# L298_motor_controller.net
KiCad netlist of a schematic drawn in EAGLE
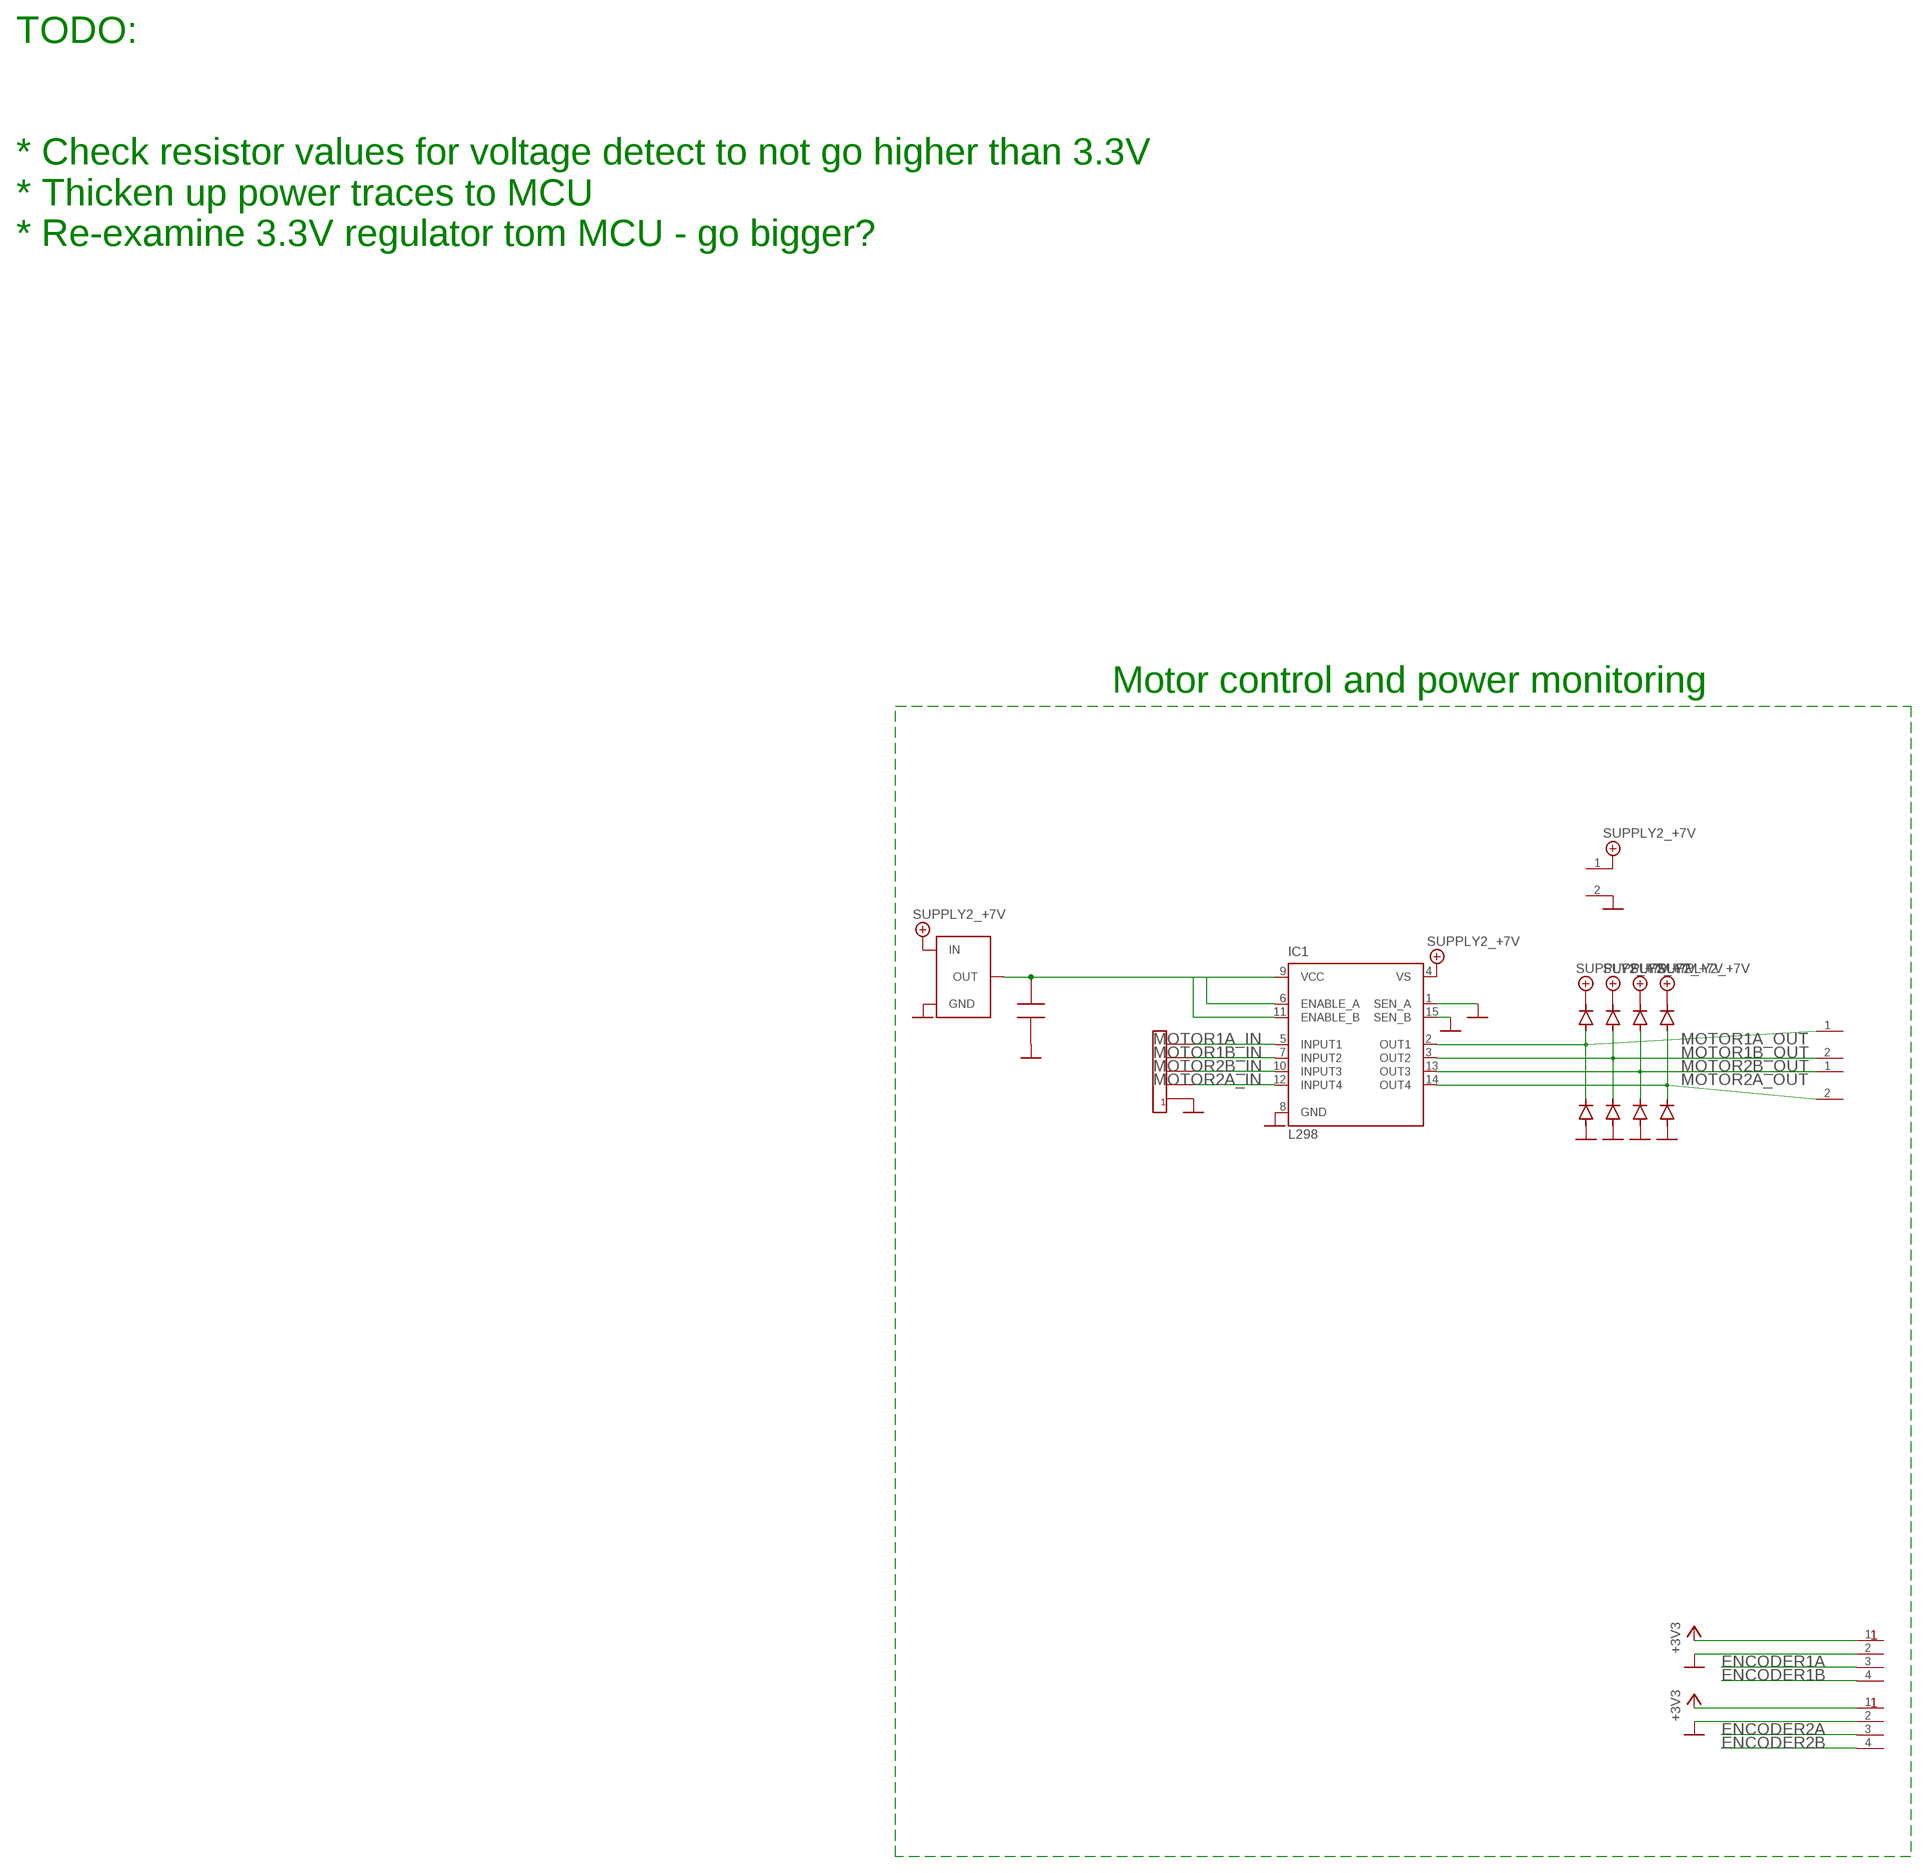
[diagram p0: schematic, sheet 1]

(export (version "E")
  (design (tool "Eeschema 10.0.6"))
  (components
    (comp (ref "IC1")
      (value "L298")
      (footprint "eagle-import:MULTIWATT-15")
      (fields (field (name "MPN") "L298N"))
      (libsource (lib "eagle-import") (part "L298"))
    )
    (comp (ref "U$1")
      (value "SCREW_TERMINAL_2_CONDUCTOR_M20109-ND")
      (footprint "eagle-import:WM20109-ND")
      (libsource (lib "eagle-import") (part "SCREW_TERMINAL_2_CONDUCTOR_M20109-ND"))
    )
    (comp (ref "U$2")
      (value "SCREW_TERMINAL_2_CONDUCTOR_M20109-ND")
      (footprint "eagle-import:WM20109-ND")
      (libsource (lib "eagle-import") (part "SCREW_TERMINAL_2_CONDUCTOR_M20109-ND"))
    )
    (comp (ref "U$3")
      (value "CONNECTOR_5_PIN")
      (footprint "eagle-import:JST_5_PIN_PH_SERIES")
      (libsource (lib "eagle-import") (part "CONNECTOR_5_PIN"))
    )
    (comp (ref "U$4")
      (value "SCREW_TERMINAL_2_CONDUCTOR_M20109-ND")
      (footprint "eagle-import:WM20109-ND")
      (libsource (lib "eagle-import") (part "SCREW_TERMINAL_2_CONDUCTOR_M20109-ND"))
    )
    (comp (ref "U$13")
      (value "DIODESOD-123FL")
      (footprint "eagle-import:SOD-123FL")
      (libsource (lib "eagle-import") (part "DIODESOD-123FL"))
    )
    (comp (ref "U$14")
      (value "DIODESOD-123FL")
      (footprint "eagle-import:SOD-123FL")
      (libsource (lib "eagle-import") (part "DIODESOD-123FL"))
    )
    (comp (ref "U$16")
      (value "DIODESOD-123FL")
      (footprint "eagle-import:SOD-123FL")
      (libsource (lib "eagle-import") (part "DIODESOD-123FL"))
    )
    (comp (ref "U$18")
      (value "DIODESOD-123FL")
      (footprint "eagle-import:SOD-123FL")
      (libsource (lib "eagle-import") (part "DIODESOD-123FL"))
    )
    (comp (ref "U$19")
      (value "DIODESOD-123FL")
      (footprint "eagle-import:SOD-123FL")
      (libsource (lib "eagle-import") (part "DIODESOD-123FL"))
    )
    (comp (ref "U$20")
      (value "DIODESOD-123FL")
      (footprint "eagle-import:SOD-123FL")
      (libsource (lib "eagle-import") (part "DIODESOD-123FL"))
    )
    (comp (ref "U$21")
      (value "DIODESOD-123FL")
      (footprint "eagle-import:SOD-123FL")
      (libsource (lib "eagle-import") (part "DIODESOD-123FL"))
    )
    (comp (ref "U$22")
      (value "DIODESOD-123FL")
      (footprint "eagle-import:SOD-123FL")
      (libsource (lib "eagle-import") (part "DIODESOD-123FL"))
    )
    (comp (ref "U$25")
      (value "VOLTAGE_REGULATOR_3_TERMINALMCP1799_SOT23")
      (footprint "eagle-import:SOT23")
      (libsource (lib "eagle-import") (part "VOLTAGE_REGULATOR_3_TERMINALMCP1799_SOT23"))
    )
    (comp (ref "U$26")
      (value "CAPACITOR0805")
      (footprint "eagle-import:0805")
      (libsource (lib "eagle-import") (part "CAPACITOR0805"))
    )
    (comp (ref "U$46")
      (value "CONNECTOR_4_PINJST_PH_SERIES")
      (footprint "eagle-import:JST_4_PIN_PH_SERIES")
      (libsource (lib "eagle-import") (part "CONNECTOR_4_PINJST_PH_SERIES"))
    )
    (comp (ref "U$49")
      (value "CONNECTOR_4_PINJST_PH_SERIES")
      (footprint "eagle-import:JST_4_PIN_PH_SERIES")
      (libsource (lib "eagle-import") (part "CONNECTOR_4_PINJST_PH_SERIES"))
    )
  )
  (nets
    (net (code "1") (name "+3V3") (class "Default")
      (node (ref "U$46") (pin "1") (pinfunction "P$1_1") (pintype "bidirectional"))
      (node (ref "U$49") (pin "1") (pinfunction "P$1_1") (pintype "bidirectional"))
    )
    (net (code "2") (name "/ENCODER1A") (class "Default")
      (node (ref "U$46") (pin "3") (pinfunction "P$3_3") (pintype "bidirectional"))
    )
    (net (code "3") (name "/ENCODER1B") (class "Default")
      (node (ref "U$46") (pin "4") (pinfunction "P$4_4") (pintype "bidirectional"))
    )
    (net (code "4") (name "/ENCODER2A") (class "Default")
      (node (ref "U$49") (pin "3") (pinfunction "P$3_3") (pintype "bidirectional"))
    )
    (net (code "5") (name "/ENCODER2B") (class "Default")
      (node (ref "U$49") (pin "4") (pinfunction "P$4_4") (pintype "bidirectional"))
    )
    (net (code "6") (name "/MOTOR1A_IN") (class "Default")
      (node (ref "IC1") (pin "5") (pinfunction "INPUT1_5") (pintype "input"))
      (node (ref "U$3") (pin "5") (pinfunction "P$5_5") (pintype "bidirectional"))
    )
    (net (code "7") (name "/MOTOR1A_OUT") (class "Default")
      (node (ref "IC1") (pin "2") (pinfunction "OUT1_2") (pintype "output"))
      (node (ref "U$1") (pin "1") (pinfunction "P$1_1") (pintype "bidirectional"))
      (node (ref "U$13") (pin "A") (pinfunction "A_A") (pintype "bidirectional"))
      (node (ref "U$19") (pin "C") (pinfunction "C_C") (pintype "bidirectional"))
    )
    (net (code "8") (name "/MOTOR1B_IN") (class "Default")
      (node (ref "IC1") (pin "7") (pinfunction "INPUT2_7") (pintype "input"))
      (node (ref "U$3") (pin "4") (pinfunction "P$4_4") (pintype "bidirectional"))
    )
    (net (code "9") (name "/MOTOR1B_OUT") (class "Default")
      (node (ref "IC1") (pin "3") (pinfunction "OUT2_3") (pintype "output"))
      (node (ref "U$1") (pin "2") (pinfunction "P$2_2") (pintype "bidirectional"))
      (node (ref "U$14") (pin "A") (pinfunction "A_A") (pintype "bidirectional"))
      (node (ref "U$20") (pin "C") (pinfunction "C_C") (pintype "bidirectional"))
    )
    (net (code "10") (name "/MOTOR2A_IN") (class "Default")
      (node (ref "IC1") (pin "12") (pinfunction "INPUT4_12") (pintype "input"))
      (node (ref "U$3") (pin "2") (pinfunction "P$2_2") (pintype "bidirectional"))
    )
    (net (code "11") (name "/MOTOR2A_OUT") (class "Default")
      (node (ref "IC1") (pin "14") (pinfunction "OUT4_14") (pintype "output"))
      (node (ref "U$18") (pin "A") (pinfunction "A_A") (pintype "bidirectional"))
      (node (ref "U$2") (pin "2") (pinfunction "P$2_2") (pintype "bidirectional"))
      (node (ref "U$22") (pin "C") (pinfunction "C_C") (pintype "bidirectional"))
    )
    (net (code "12") (name "/MOTOR2B_IN") (class "Default")
      (node (ref "IC1") (pin "10") (pinfunction "INPUT3_10") (pintype "input"))
      (node (ref "U$3") (pin "3") (pinfunction "P$3_3") (pintype "bidirectional"))
    )
    (net (code "13") (name "/MOTOR2B_OUT") (class "Default")
      (node (ref "IC1") (pin "13") (pinfunction "OUT3_13") (pintype "output"))
      (node (ref "U$16") (pin "A") (pinfunction "A_A") (pintype "bidirectional"))
      (node (ref "U$2") (pin "1") (pinfunction "P$1_1") (pintype "bidirectional"))
      (node (ref "U$21") (pin "C") (pinfunction "C_C") (pintype "bidirectional"))
    )
    (net (code "14") (name "Net-(IC1-ENABLE_A)") (class "Default")
      (node (ref "IC1") (pin "11") (pinfunction "ENABLE_B_11") (pintype "input"))
      (node (ref "IC1") (pin "6") (pinfunction "ENABLE_A_6") (pintype "input"))
      (node (ref "IC1") (pin "9") (pinfunction "VCC_9") (pintype "power_in"))
      (node (ref "U$25") (pin "2") (pinfunction "OUT_2") (pintype "bidirectional"))
      (node (ref "U$26") (pin "P$3") (pinfunction "2-_P$3") (pintype "bidirectional"))
    )
    (net (code "15") (name "SUPPLY1_GND") (class "Default")
      (node (ref "IC1") (pin "1") (pinfunction "SEN_A_1") (pintype "input"))
      (node (ref "IC1") (pin "15") (pinfunction "SEN_B_15") (pintype "input"))
      (node (ref "IC1") (pin "8") (pinfunction "GND_8") (pintype "power_in"))
      (node (ref "U$19") (pin "A") (pinfunction "A_A") (pintype "bidirectional"))
      (node (ref "U$20") (pin "A") (pinfunction "A_A") (pintype "bidirectional"))
      (node (ref "U$21") (pin "A") (pinfunction "A_A") (pintype "bidirectional"))
      (node (ref "U$22") (pin "A") (pinfunction "A_A") (pintype "bidirectional"))
      (node (ref "U$25") (pin "1") (pinfunction "GND_1") (pintype "bidirectional"))
      (node (ref "U$26") (pin "P$2") (pinfunction "1+_P$2") (pintype "bidirectional"))
      (node (ref "U$3") (pin "1") (pinfunction "P$1_1") (pintype "bidirectional"))
      (node (ref "U$46") (pin "2") (pinfunction "P$2_2") (pintype "bidirectional"))
      (node (ref "U$49") (pin "2") (pinfunction "P$2_2") (pintype "bidirectional"))
    )
    (net (code "16") (name "SUPPLY2_+7V") (class "Default")
      (node (ref "IC1") (pin "4") (pinfunction "VS_4") (pintype "power_in"))
      (node (ref "U$13") (pin "C") (pinfunction "C_C") (pintype "bidirectional"))
      (node (ref "U$14") (pin "C") (pinfunction "C_C") (pintype "bidirectional"))
      (node (ref "U$16") (pin "C") (pinfunction "C_C") (pintype "bidirectional"))
      (node (ref "U$18") (pin "C") (pinfunction "C_C") (pintype "bidirectional"))
      (node (ref "U$25") (pin "3") (pinfunction "IN_3") (pintype "bidirectional"))
    )
    (net (code "17") (name "unconnected-(U$4-P$1-Pad1)") (class "Default")
      (node (ref "U$4") (pin "1") (pinfunction "P$1_1") (pintype "bidirectional"))
    )
    (net (code "18") (name "unconnected-(U$4-P$2-Pad2)") (class "Default")
      (node (ref "U$4") (pin "2") (pinfunction "P$2_2") (pintype "bidirectional"))
    )
  )
)
